# six4mix_power.net
KiCad netlist of a schematic drawn in EAGLE
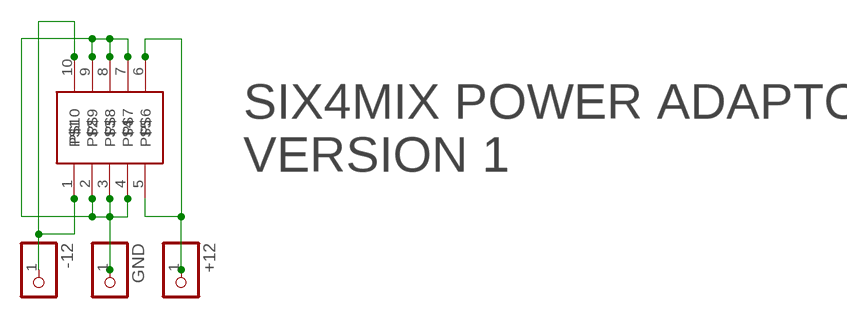
[diagram p0: schematic, sheet 1]

(export (version "E")
  (design (tool "Eeschema 10.0.6"))
  (components
    (comp (ref "+12")
      (value "PINHD-1X1")
      (footprint "eagle-import:1X01")
      (libsource (lib "eagle-import") (part "PINHD-1X1"))
    )
    (comp (ref "-12")
      (value "PINHD-1X1")
      (footprint "eagle-import:1X01")
      (libsource (lib "eagle-import") (part "PINHD-1X1"))
    )
    (comp (ref "GND")
      (value "PINHD-1X1")
      (footprint "eagle-import:1X01")
      (libsource (lib "eagle-import") (part "PINHD-1X1"))
    )
    (comp (ref "U$1")
      (value "2X5SMT")
      (footprint "eagle-import:2X5SMT")
      (libsource (lib "eagle-import") (part "2X5SMT"))
    )
  )
  (nets
    (net (code "1") (name "Net-(U$1-P$1)") (class "Default")
      (node (ref "-12") (pin "1") (pinfunction "1_1") (pintype "passive"))
      (node (ref "U$1") (pin "1") (pinfunction "P$1_1") (pintype "bidirectional"))
      (node (ref "U$1") (pin "10") (pinfunction "P$10_10") (pintype "bidirectional"))
    )
    (net (code "2") (name "Net-(U$1-P$2)") (class "Default")
      (node (ref "GND") (pin "1") (pinfunction "1_1") (pintype "passive"))
      (node (ref "U$1") (pin "2") (pinfunction "P$2_2") (pintype "bidirectional"))
      (node (ref "U$1") (pin "3") (pinfunction "P$3_3") (pintype "bidirectional"))
      (node (ref "U$1") (pin "4") (pinfunction "P$4_4") (pintype "bidirectional"))
      (node (ref "U$1") (pin "7") (pinfunction "P$7_7") (pintype "bidirectional"))
      (node (ref "U$1") (pin "8") (pinfunction "P$8_8") (pintype "bidirectional"))
      (node (ref "U$1") (pin "9") (pinfunction "P$9_9") (pintype "bidirectional"))
    )
    (net (code "3") (name "Net-(U$1-P$5)") (class "Default")
      (node (ref "+12") (pin "1") (pinfunction "1_1") (pintype "passive"))
      (node (ref "U$1") (pin "5") (pinfunction "P$5_5") (pintype "bidirectional"))
      (node (ref "U$1") (pin "6") (pinfunction "P$6_6") (pintype "bidirectional"))
    )
  )
)
